# PCB_Schematic.net
KiCad netlist of a schematic drawn in Altium Designer
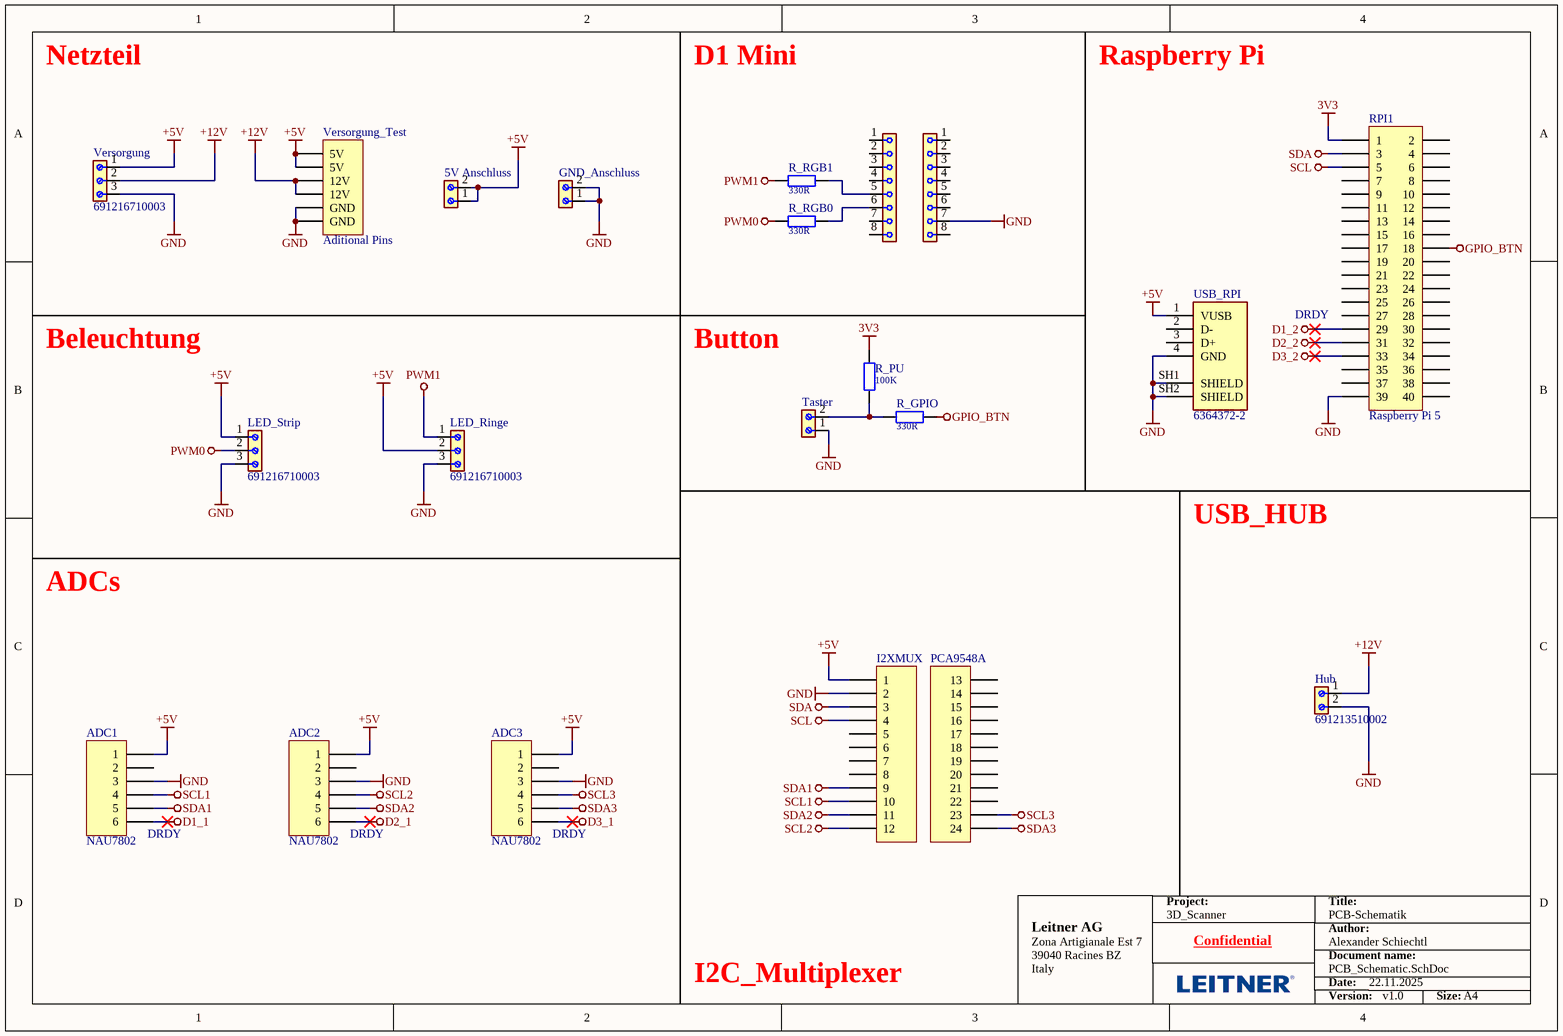
[diagram p0: PCB_Schematic.SchDoc]

(export (version "E")
  (design (tool "Eeschema 10.0.6"))
  (components
    (comp (ref "5V Anschluss")
      (value "691213510002")
      (footprint "691213510002")
      (description "2 Position Wire to Board Terminal Block Horizontal with Board 0.200 (5.08mm) Through Hole")
      (fields (field (name "MF") "WÃ¼rth Elektronik"))
      (libsource (lib "691213510002") (part "691213510002"))
    )
    (comp (ref "ADC1")
      (value "NAU7802")
      (footprint "HDR1X6")
      (description "Header, 6-Pin")
      (fields (field (name "PUBLISHER") "Altium Limited"))
      (libsource (lib "Miscellaneous Connectors") (part "Header 6"))
    )
    (comp (ref "ADC2")
      (value "NAU7802")
      (footprint "HDR1X6")
      (description "Header, 6-Pin")
      (fields (field (name "PUBLISHER") "Altium Limited"))
      (libsource (lib "Miscellaneous Connectors") (part "Header 6"))
    )
    (comp (ref "ADC3")
      (value "NAU7802")
      (footprint "HDR1X6")
      (description "Header, 6-Pin")
      (fields (field (name "PUBLISHER") "Altium Limited"))
      (libsource (lib "Miscellaneous Connectors") (part "Header 6"))
    )
    (comp (ref "ESP1")
      (value "6130XX11821_61300811821")
      (footprint "61300811821")
      (fields (field (name "MF") "WÃ¼rth Elektronik") (field (name "MP") "61300811821"))
      (libsource (lib "") (part "6130XX11821_61300811821_1"))
    )
    (comp (ref "ESP2")
      (value "6130XX11821_61300811821")
      (footprint "61300811821")
      (fields (field (name "MF") "WÃ¼rth Elektronik") (field (name "MP") "61300811821"))
      (libsource (lib "Header8") (part "6130XX11821_61300811821"))
    )
    (comp (ref "GND_Anschluss")
      (value "691213510002")
      (footprint "691213510002")
      (description "2 Position Wire to Board Terminal Block Horizontal with Board 0.200 (5.08mm) Through Hole")
      (fields (field (name "MF") "WÃ¼rth Elektronik"))
      (libsource (lib "691213510002") (part "691213510002"))
    )
    (comp (ref "Hub")
      (value "691213510002")
      (footprint "691213510002")
      (description "2 Position Wire to Board Terminal Block Horizontal with Board 0.200 (5.08mm) Through Hole")
      (fields (field (name "MF") "WÃ¼rth Elektronik"))
      (libsource (lib "") (part "691213510002_1"))
    )
    (comp (ref "I2XMUX")
      (value "Header 12")
      (footprint "HDR1X12")
      (description "Header, 12-Pin")
      (fields (field (name "PUBLISHER") "Altium Limited"))
      (libsource (lib "Miscellaneous Connectors") (part "Header 12"))
    )
    (comp (ref "LED_Ringe")
      (value "691216710003")
      (footprint "691216710003:691216710003")
      (description "5.00 MM TERMINAL BLOCK;")
      (fields (field (name "MF") "WÃ¼rth Elektronik"))
      (libsource (lib "") (part "691216710003_1"))
    )
    (comp (ref "LED_Strip")
      (value "691216710003")
      (footprint "691216710003:691216710003")
      (description "5.00 MM TERMINAL BLOCK;")
      (fields (field (name "MF") "WÃ¼rth Elektronik"))
      (libsource (lib "") (part "691216710003_1"))
    )
    (comp (ref "PCA9548A")
      (value "Header 12")
      (footprint "HDR1X12")
      (description "Header, 12-Pin")
      (fields (field (name "PUBLISHER") "Altium Limited"))
      (libsource (lib "") (part "Header 12_1"))
    )
    (comp (ref "RPI1")
      (value "Raspberry Pi 5")
      (footprint "HDR2X20")
      (description "Header, 20-Pin, Dual row")
      (fields (field (name "PUBLISHER") "Altium Limited"))
      (libsource (lib "Miscellaneous Connectors") (part "Header 20X2"))
    )
    (comp (ref "R_GPIO")
      (value "330R")
      (footprint "R_0207/RM4")
      (description "Resistor")
      (libsource (lib "HTLInn_RLCQ") (part "R"))
    )
    (comp (ref "R_PU")
      (value "100K")
      (footprint "R_0207/RM4")
      (description "Resistor")
      (libsource (lib "") (part "R_1"))
    )
    (comp (ref "R_RGB0")
      (value "330R")
      (footprint "R_0207/RM4")
      (description "Resistor")
      (libsource (lib "HTLInn_RLCQ") (part "R"))
    )
    (comp (ref "R_RGB1")
      (value "330R")
      (footprint "R_0207/RM4")
      (description "Resistor")
      (libsource (lib "HTLInn_RLCQ") (part "R"))
    )
    (comp (ref "Taster")
      (value "691213510002")
      (footprint "691213510002")
      (description "2 Position Wire to Board Terminal Block Horizontal with Board 0.200 (5.08mm) Through Hole")
      (fields (field (name "MF") "WÃ¼rth Elektronik"))
      (libsource (lib "691213510002") (part "691213510002"))
    )
    (comp (ref "USB_RPI")
      (value "6364372-2")
      (footprint "TE_6364372-2")
      (description "Conn USB 2.0 Type A RCP 4 POS Solder RA Thru-Hole 4 Terminal 1 Port Box/Tube")
      (fields (field (name "MF") "TE Connectivity") (field (name "DIGI-KEY_PART_NUMBER") "A122647-ND"))
      (libsource (lib "6364372-2") (part "6364372-2"))
    )
    (comp (ref "Versorgung")
      (value "691216710003")
      (footprint "691216710003:691216710003")
      (description "5.00 MM TERMINAL BLOCK;")
      (fields (field (name "MF") "WÃ¼rth Elektronik"))
      (libsource (lib "691216710003") (part "691216710003"))
    )
    (comp (ref "Versorgung_Test")
      (value "Aditional Pins")
      (footprint "HDR1X6")
      (description "Header, 6-Pin")
      (fields (field (name "PUBLISHER") "Altium Limited"))
      (libsource (lib "") (part "Header 6_1"))
    )
  )
  (nets
    (net (code "1") (name "+5V") (class "Default")
      (node (ref "5V Anschluss") (pin "1") (pinfunction "1_1") (pintype "passive"))
      (node (ref "5V Anschluss") (pin "2") (pinfunction "2_2") (pintype "passive"))
      (node (ref "ADC1") (pin "1") (pinfunction "1_1") (pintype "passive"))
      (node (ref "ADC2") (pin "1") (pinfunction "1_1") (pintype "passive"))
      (node (ref "ADC3") (pin "1") (pinfunction "1_1") (pintype "passive"))
      (node (ref "I2XMUX") (pin "1") (pinfunction "1_1") (pintype "passive"))
      (node (ref "LED_Ringe") (pin "2") (pinfunction "2_2") (pintype "passive"))
      (node (ref "LED_Strip") (pin "1") (pinfunction "1_1") (pintype "passive"))
      (node (ref "USB_RPI") (pin "1") (pinfunction "VUSB_1") (pintype "passive"))
      (node (ref "Versorgung") (pin "1") (pinfunction "1_1") (pintype "passive"))
      (node (ref "Versorgung_Test") (pin "5") (pinfunction "5V_5") (pintype "passive"))
      (node (ref "Versorgung_Test") (pin "6") (pinfunction "5V_6") (pintype "passive"))
    )
    (net (code "2") (name "+12V") (class "Default")
      (node (ref "Hub") (pin "1") (pinfunction "1_1") (pintype "passive"))
      (node (ref "Versorgung") (pin "2") (pinfunction "2_2") (pintype "passive"))
      (node (ref "Versorgung_Test") (pin "3") (pinfunction "12V_3") (pintype "passive"))
      (node (ref "Versorgung_Test") (pin "4") (pinfunction "12V_4") (pintype "passive"))
    )
    (net (code "3") (name "3V3") (class "Default")
      (node (ref "RPI1") (pin "1") (pinfunction "1_1") (pintype "passive"))
      (node (ref "R_PU") (pin "1") (pinfunction "1_1") (pintype "passive"))
    )
    (net (code "4") (name "D1_1") (class "Default")
      (node (ref "ADC1") (pin "6") (pinfunction "6_6") (pintype "passive"))
    )
    (net (code "5") (name "D1_2") (class "Default")
      (node (ref "RPI1") (pin "29") (pinfunction "29_29") (pintype "passive"))
    )
    (net (code "6") (name "D2_1") (class "Default")
      (node (ref "ADC2") (pin "6") (pinfunction "6_6") (pintype "passive"))
    )
    (net (code "7") (name "D2_2") (class "Default")
      (node (ref "RPI1") (pin "31") (pinfunction "31_31") (pintype "passive"))
    )
    (net (code "8") (name "D3_1") (class "Default")
      (node (ref "ADC3") (pin "6") (pinfunction "6_6") (pintype "passive"))
    )
    (net (code "9") (name "D3_2") (class "Default")
      (node (ref "RPI1") (pin "33") (pinfunction "33_33") (pintype "passive"))
    )
    (net (code "10") (name "GND") (class "Default")
      (node (ref "ADC1") (pin "3") (pinfunction "3_3") (pintype "passive"))
      (node (ref "ADC2") (pin "3") (pinfunction "3_3") (pintype "passive"))
      (node (ref "ADC3") (pin "3") (pinfunction "3_3") (pintype "passive"))
      (node (ref "ESP2") (pin "7") (pinfunction "7_7") (pintype "passive"))
      (node (ref "GND_Anschluss") (pin "1") (pinfunction "1_1") (pintype "passive"))
      (node (ref "GND_Anschluss") (pin "2") (pinfunction "2_2") (pintype "passive"))
      (node (ref "Hub") (pin "2") (pinfunction "2_2") (pintype "passive"))
      (node (ref "I2XMUX") (pin "2") (pinfunction "2_2") (pintype "passive"))
      (node (ref "LED_Ringe") (pin "3") (pinfunction "3_3") (pintype "passive"))
      (node (ref "LED_Strip") (pin "3") (pinfunction "3_3") (pintype "passive"))
      (node (ref "RPI1") (pin "39") (pinfunction "39_39") (pintype "passive"))
      (node (ref "Taster") (pin "1") (pinfunction "1_1") (pintype "passive"))
      (node (ref "USB_RPI") (pin "4") (pinfunction "GND_4") (pintype "passive"))
      (node (ref "USB_RPI") (pin "SH1") (pinfunction "SHIELD_SH1") (pintype "passive"))
      (node (ref "USB_RPI") (pin "SH2") (pinfunction "SHIELD_SH2") (pintype "passive"))
      (node (ref "Versorgung") (pin "3") (pinfunction "3_3") (pintype "passive"))
      (node (ref "Versorgung_Test") (pin "1") (pinfunction "GND_1") (pintype "passive"))
      (node (ref "Versorgung_Test") (pin "2") (pinfunction "GND_2") (pintype "passive"))
    )
    (net (code "11") (name "GPIO_BTN") (class "Default")
      (node (ref "RPI1") (pin "18") (pinfunction "18_18") (pintype "passive"))
      (node (ref "R_GPIO") (pin "1") (pinfunction "1_1") (pintype "passive"))
    )
    (net (code "12") (name "Net-(ESP1-Pad5)") (class "Default")
      (node (ref "ESP1") (pin "5") (pinfunction "5_5") (pintype "passive"))
      (node (ref "R_RGB1") (pin "1") (pinfunction "1_1") (pintype "passive"))
    )
    (net (code "13") (name "Net-(ESP1-Pad6)") (class "Default")
      (node (ref "ESP1") (pin "6") (pinfunction "6_6") (pintype "passive"))
      (node (ref "R_RGB0") (pin "1") (pinfunction "1_1") (pintype "passive"))
    )
    (net (code "14") (name "Net-(R_GPIO-Pad2)") (class "Default")
      (node (ref "R_GPIO") (pin "2") (pinfunction "2_2") (pintype "passive"))
      (node (ref "R_PU") (pin "2") (pinfunction "2_2") (pintype "passive"))
      (node (ref "Taster") (pin "2") (pinfunction "2_2") (pintype "passive"))
    )
    (net (code "15") (name "PWM0") (class "Default")
      (node (ref "LED_Strip") (pin "2") (pinfunction "2_2") (pintype "passive"))
      (node (ref "R_RGB0") (pin "2") (pinfunction "2_2") (pintype "passive"))
    )
    (net (code "16") (name "PWM1") (class "Default")
      (node (ref "LED_Ringe") (pin "1") (pinfunction "1_1") (pintype "passive"))
      (node (ref "R_RGB1") (pin "2") (pinfunction "2_2") (pintype "passive"))
    )
    (net (code "17") (name "SCL") (class "Default")
      (node (ref "I2XMUX") (pin "4") (pinfunction "4_4") (pintype "passive"))
      (node (ref "RPI1") (pin "5") (pinfunction "5_5") (pintype "passive"))
    )
    (net (code "18") (name "SCL1") (class "Default")
      (node (ref "ADC1") (pin "4") (pinfunction "4_4") (pintype "passive"))
      (node (ref "I2XMUX") (pin "10") (pinfunction "10_10") (pintype "passive"))
    )
    (net (code "19") (name "SCL2") (class "Default")
      (node (ref "ADC2") (pin "4") (pinfunction "4_4") (pintype "passive"))
      (node (ref "I2XMUX") (pin "12") (pinfunction "12_12") (pintype "passive"))
    )
    (net (code "20") (name "SCL3") (class "Default")
      (node (ref "ADC3") (pin "4") (pinfunction "4_4") (pintype "passive"))
      (node (ref "PCA9548A") (pin "11") (pinfunction "23_11") (pintype "passive"))
    )
    (net (code "21") (name "SDA") (class "Default")
      (node (ref "I2XMUX") (pin "3") (pinfunction "3_3") (pintype "passive"))
      (node (ref "RPI1") (pin "3") (pinfunction "3_3") (pintype "passive"))
    )
    (net (code "22") (name "SDA1") (class "Default")
      (node (ref "ADC1") (pin "5") (pinfunction "5_5") (pintype "passive"))
      (node (ref "I2XMUX") (pin "9") (pinfunction "9_9") (pintype "passive"))
    )
    (net (code "23") (name "SDA2") (class "Default")
      (node (ref "ADC2") (pin "5") (pinfunction "5_5") (pintype "passive"))
      (node (ref "I2XMUX") (pin "11") (pinfunction "11_11") (pintype "passive"))
    )
    (net (code "24") (name "SDA3") (class "Default")
      (node (ref "ADC3") (pin "5") (pinfunction "5_5") (pintype "passive"))
      (node (ref "PCA9548A") (pin "12") (pinfunction "24_12") (pintype "passive"))
    )
    (net (code "25") (name "unconnected-(ADC1-Pad2)") (class "Default")
      (node (ref "ADC1") (pin "2") (pinfunction "2_2") (pintype "passive"))
    )
    (net (code "26") (name "unconnected-(ADC2-Pad2)") (class "Default")
      (node (ref "ADC2") (pin "2") (pinfunction "2_2") (pintype "passive"))
    )
    (net (code "27") (name "unconnected-(ADC3-Pad2)") (class "Default")
      (node (ref "ADC3") (pin "2") (pinfunction "2_2") (pintype "passive"))
    )
    (net (code "28") (name "unconnected-(ESP1-Pad1)") (class "Default")
      (node (ref "ESP1") (pin "1") (pinfunction "1_1") (pintype "passive"))
    )
    (net (code "29") (name "unconnected-(ESP1-Pad2)") (class "Default")
      (node (ref "ESP1") (pin "2") (pinfunction "2_2") (pintype "passive"))
    )
    (net (code "30") (name "unconnected-(ESP1-Pad3)") (class "Default")
      (node (ref "ESP1") (pin "3") (pinfunction "3_3") (pintype "passive"))
    )
    (net (code "31") (name "unconnected-(ESP1-Pad4)") (class "Default")
      (node (ref "ESP1") (pin "4") (pinfunction "4_4") (pintype "passive"))
    )
    (net (code "32") (name "unconnected-(ESP1-Pad7)") (class "Default")
      (node (ref "ESP1") (pin "7") (pinfunction "7_7") (pintype "passive"))
    )
    (net (code "33") (name "unconnected-(ESP1-Pad8)") (class "Default")
      (node (ref "ESP1") (pin "8") (pinfunction "8_8") (pintype "passive"))
    )
    (net (code "34") (name "unconnected-(ESP2-Pad1)") (class "Default")
      (node (ref "ESP2") (pin "1") (pinfunction "1_1") (pintype "passive"))
    )
    (net (code "35") (name "unconnected-(ESP2-Pad2)") (class "Default")
      (node (ref "ESP2") (pin "2") (pinfunction "2_2") (pintype "passive"))
    )
    (net (code "36") (name "unconnected-(ESP2-Pad3)") (class "Default")
      (node (ref "ESP2") (pin "3") (pinfunction "3_3") (pintype "passive"))
    )
    (net (code "37") (name "unconnected-(ESP2-Pad4)") (class "Default")
      (node (ref "ESP2") (pin "4") (pinfunction "4_4") (pintype "passive"))
    )
    (net (code "38") (name "unconnected-(ESP2-Pad5)") (class "Default")
      (node (ref "ESP2") (pin "5") (pinfunction "5_5") (pintype "passive"))
    )
    (net (code "39") (name "unconnected-(ESP2-Pad6)") (class "Default")
      (node (ref "ESP2") (pin "6") (pinfunction "6_6") (pintype "passive"))
    )
    (net (code "40") (name "unconnected-(ESP2-Pad8)") (class "Default")
      (node (ref "ESP2") (pin "8") (pinfunction "8_8") (pintype "passive"))
    )
    (net (code "41") (name "unconnected-(I2XMUX-Pad5)") (class "Default")
      (node (ref "I2XMUX") (pin "5") (pinfunction "5_5") (pintype "passive"))
    )
    (net (code "42") (name "unconnected-(I2XMUX-Pad6)") (class "Default")
      (node (ref "I2XMUX") (pin "6") (pinfunction "6_6") (pintype "passive"))
    )
    (net (code "43") (name "unconnected-(I2XMUX-Pad7)") (class "Default")
      (node (ref "I2XMUX") (pin "7") (pinfunction "7_7") (pintype "passive"))
    )
    (net (code "44") (name "unconnected-(I2XMUX-Pad8)") (class "Default")
      (node (ref "I2XMUX") (pin "8") (pinfunction "8_8") (pintype "passive"))
    )
    (net (code "45") (name "unconnected-(PCA9548A-13-Pad1)") (class "Default")
      (node (ref "PCA9548A") (pin "1") (pinfunction "13_1") (pintype "passive"))
    )
    (net (code "46") (name "unconnected-(PCA9548A-14-Pad2)") (class "Default")
      (node (ref "PCA9548A") (pin "2") (pinfunction "14_2") (pintype "passive"))
    )
    (net (code "47") (name "unconnected-(PCA9548A-15-Pad3)") (class "Default")
      (node (ref "PCA9548A") (pin "3") (pinfunction "15_3") (pintype "passive"))
    )
    (net (code "48") (name "unconnected-(PCA9548A-16-Pad4)") (class "Default")
      (node (ref "PCA9548A") (pin "4") (pinfunction "16_4") (pintype "passive"))
    )
    (net (code "49") (name "unconnected-(PCA9548A-17-Pad5)") (class "Default")
      (node (ref "PCA9548A") (pin "5") (pinfunction "17_5") (pintype "passive"))
    )
    (net (code "50") (name "unconnected-(PCA9548A-18-Pad6)") (class "Default")
      (node (ref "PCA9548A") (pin "6") (pinfunction "18_6") (pintype "passive"))
    )
    (net (code "51") (name "unconnected-(PCA9548A-19-Pad7)") (class "Default")
      (node (ref "PCA9548A") (pin "7") (pinfunction "19_7") (pintype "passive"))
    )
    (net (code "52") (name "unconnected-(PCA9548A-20-Pad8)") (class "Default")
      (node (ref "PCA9548A") (pin "8") (pinfunction "20_8") (pintype "passive"))
    )
    (net (code "53") (name "unconnected-(PCA9548A-21-Pad9)") (class "Default")
      (node (ref "PCA9548A") (pin "9") (pinfunction "21_9") (pintype "passive"))
    )
    (net (code "54") (name "unconnected-(PCA9548A-22-Pad10)") (class "Default")
      (node (ref "PCA9548A") (pin "10") (pinfunction "22_10") (pintype "passive"))
    )
    (net (code "55") (name "unconnected-(RPI1-Pad2)") (class "Default")
      (node (ref "RPI1") (pin "2") (pinfunction "2_2") (pintype "passive"))
    )
    (net (code "56") (name "unconnected-(RPI1-Pad4)") (class "Default")
      (node (ref "RPI1") (pin "4") (pinfunction "4_4") (pintype "passive"))
    )
    (net (code "57") (name "unconnected-(RPI1-Pad6)") (class "Default")
      (node (ref "RPI1") (pin "6") (pinfunction "6_6") (pintype "passive"))
    )
    (net (code "58") (name "unconnected-(RPI1-Pad7)") (class "Default")
      (node (ref "RPI1") (pin "7") (pinfunction "7_7") (pintype "passive"))
    )
    (net (code "59") (name "unconnected-(RPI1-Pad8)") (class "Default")
      (node (ref "RPI1") (pin "8") (pinfunction "8_8") (pintype "passive"))
    )
    (net (code "60") (name "unconnected-(RPI1-Pad9)") (class "Default")
      (node (ref "RPI1") (pin "9") (pinfunction "9_9") (pintype "passive"))
    )
    (net (code "61") (name "unconnected-(RPI1-Pad10)") (class "Default")
      (node (ref "RPI1") (pin "10") (pinfunction "10_10") (pintype "passive"))
    )
    (net (code "62") (name "unconnected-(RPI1-Pad11)") (class "Default")
      (node (ref "RPI1") (pin "11") (pinfunction "11_11") (pintype "passive"))
    )
    (net (code "63") (name "unconnected-(RPI1-Pad12)") (class "Default")
      (node (ref "RPI1") (pin "12") (pinfunction "12_12") (pintype "passive"))
    )
    (net (code "64") (name "unconnected-(RPI1-Pad13)") (class "Default")
      (node (ref "RPI1") (pin "13") (pinfunction "13_13") (pintype "passive"))
    )
    (net (code "65") (name "unconnected-(RPI1-Pad14)") (class "Default")
      (node (ref "RPI1") (pin "14") (pinfunction "14_14") (pintype "passive"))
    )
    (net (code "66") (name "unconnected-(RPI1-Pad15)") (class "Default")
      (node (ref "RPI1") (pin "15") (pinfunction "15_15") (pintype "passive"))
    )
    (net (code "67") (name "unconnected-(RPI1-Pad16)") (class "Default")
      (node (ref "RPI1") (pin "16") (pinfunction "16_16") (pintype "passive"))
    )
    (net (code "68") (name "unconnected-(RPI1-Pad17)") (class "Default")
      (node (ref "RPI1") (pin "17") (pinfunction "17_17") (pintype "passive"))
    )
    (net (code "69") (name "unconnected-(RPI1-Pad19)") (class "Default")
      (node (ref "RPI1") (pin "19") (pinfunction "19_19") (pintype "passive"))
    )
    (net (code "70") (name "unconnected-(RPI1-Pad20)") (class "Default")
      (node (ref "RPI1") (pin "20") (pinfunction "20_20") (pintype "passive"))
    )
    (net (code "71") (name "unconnected-(RPI1-Pad21)") (class "Default")
      (node (ref "RPI1") (pin "21") (pinfunction "21_21") (pintype "passive"))
    )
    (net (code "72") (name "unconnected-(RPI1-Pad22)") (class "Default")
      (node (ref "RPI1") (pin "22") (pinfunction "22_22") (pintype "passive"))
    )
    (net (code "73") (name "unconnected-(RPI1-Pad23)") (class "Default")
      (node (ref "RPI1") (pin "23") (pinfunction "23_23") (pintype "passive"))
    )
    (net (code "74") (name "unconnected-(RPI1-Pad24)") (class "Default")
      (node (ref "RPI1") (pin "24") (pinfunction "24_24") (pintype "passive"))
    )
    (net (code "75") (name "unconnected-(RPI1-Pad25)") (class "Default")
      (node (ref "RPI1") (pin "25") (pinfunction "25_25") (pintype "passive"))
    )
    (net (code "76") (name "unconnected-(RPI1-Pad26)") (class "Default")
      (node (ref "RPI1") (pin "26") (pinfunction "26_26") (pintype "passive"))
    )
    (net (code "77") (name "unconnected-(RPI1-Pad27)") (class "Default")
      (node (ref "RPI1") (pin "27") (pinfunction "27_27") (pintype "passive"))
    )
    (net (code "78") (name "unconnected-(RPI1-Pad28)") (class "Default")
      (node (ref "RPI1") (pin "28") (pinfunction "28_28") (pintype "passive"))
    )
    (net (code "79") (name "unconnected-(RPI1-Pad30)") (class "Default")
      (node (ref "RPI1") (pin "30") (pinfunction "30_30") (pintype "passive"))
    )
    (net (code "80") (name "unconnected-(RPI1-Pad32)") (class "Default")
      (node (ref "RPI1") (pin "32") (pinfunction "32_32") (pintype "passive"))
    )
    (net (code "81") (name "unconnected-(RPI1-Pad34)") (class "Default")
      (node (ref "RPI1") (pin "34") (pinfunction "34_34") (pintype "passive"))
    )
    (net (code "82") (name "unconnected-(RPI1-Pad35)") (class "Default")
      (node (ref "RPI1") (pin "35") (pinfunction "35_35") (pintype "passive"))
    )
    (net (code "83") (name "unconnected-(RPI1-Pad36)") (class "Default")
      (node (ref "RPI1") (pin "36") (pinfunction "36_36") (pintype "passive"))
    )
    (net (code "84") (name "unconnected-(RPI1-Pad37)") (class "Default")
      (node (ref "RPI1") (pin "37") (pinfunction "37_37") (pintype "passive"))
    )
    (net (code "85") (name "unconnected-(RPI1-Pad38)") (class "Default")
      (node (ref "RPI1") (pin "38") (pinfunction "38_38") (pintype "passive"))
    )
    (net (code "86") (name "unconnected-(RPI1-Pad40)") (class "Default")
      (node (ref "RPI1") (pin "40") (pinfunction "40_40") (pintype "passive"))
    )
    (net (code "87") (name "unconnected-(USB_RPI-D+-Pad3)") (class "Default")
      (node (ref "USB_RPI") (pin "3") (pinfunction "D+_3") (pintype "passive"))
    )
    (net (code "88") (name "unconnected-(USB_RPI-D--Pad2)") (class "Default")
      (node (ref "USB_RPI") (pin "2") (pinfunction "D-_2") (pintype "passive"))
    )
  )
)
